# flasher.net
KiCad netlist of a schematic drawn in EAGLE
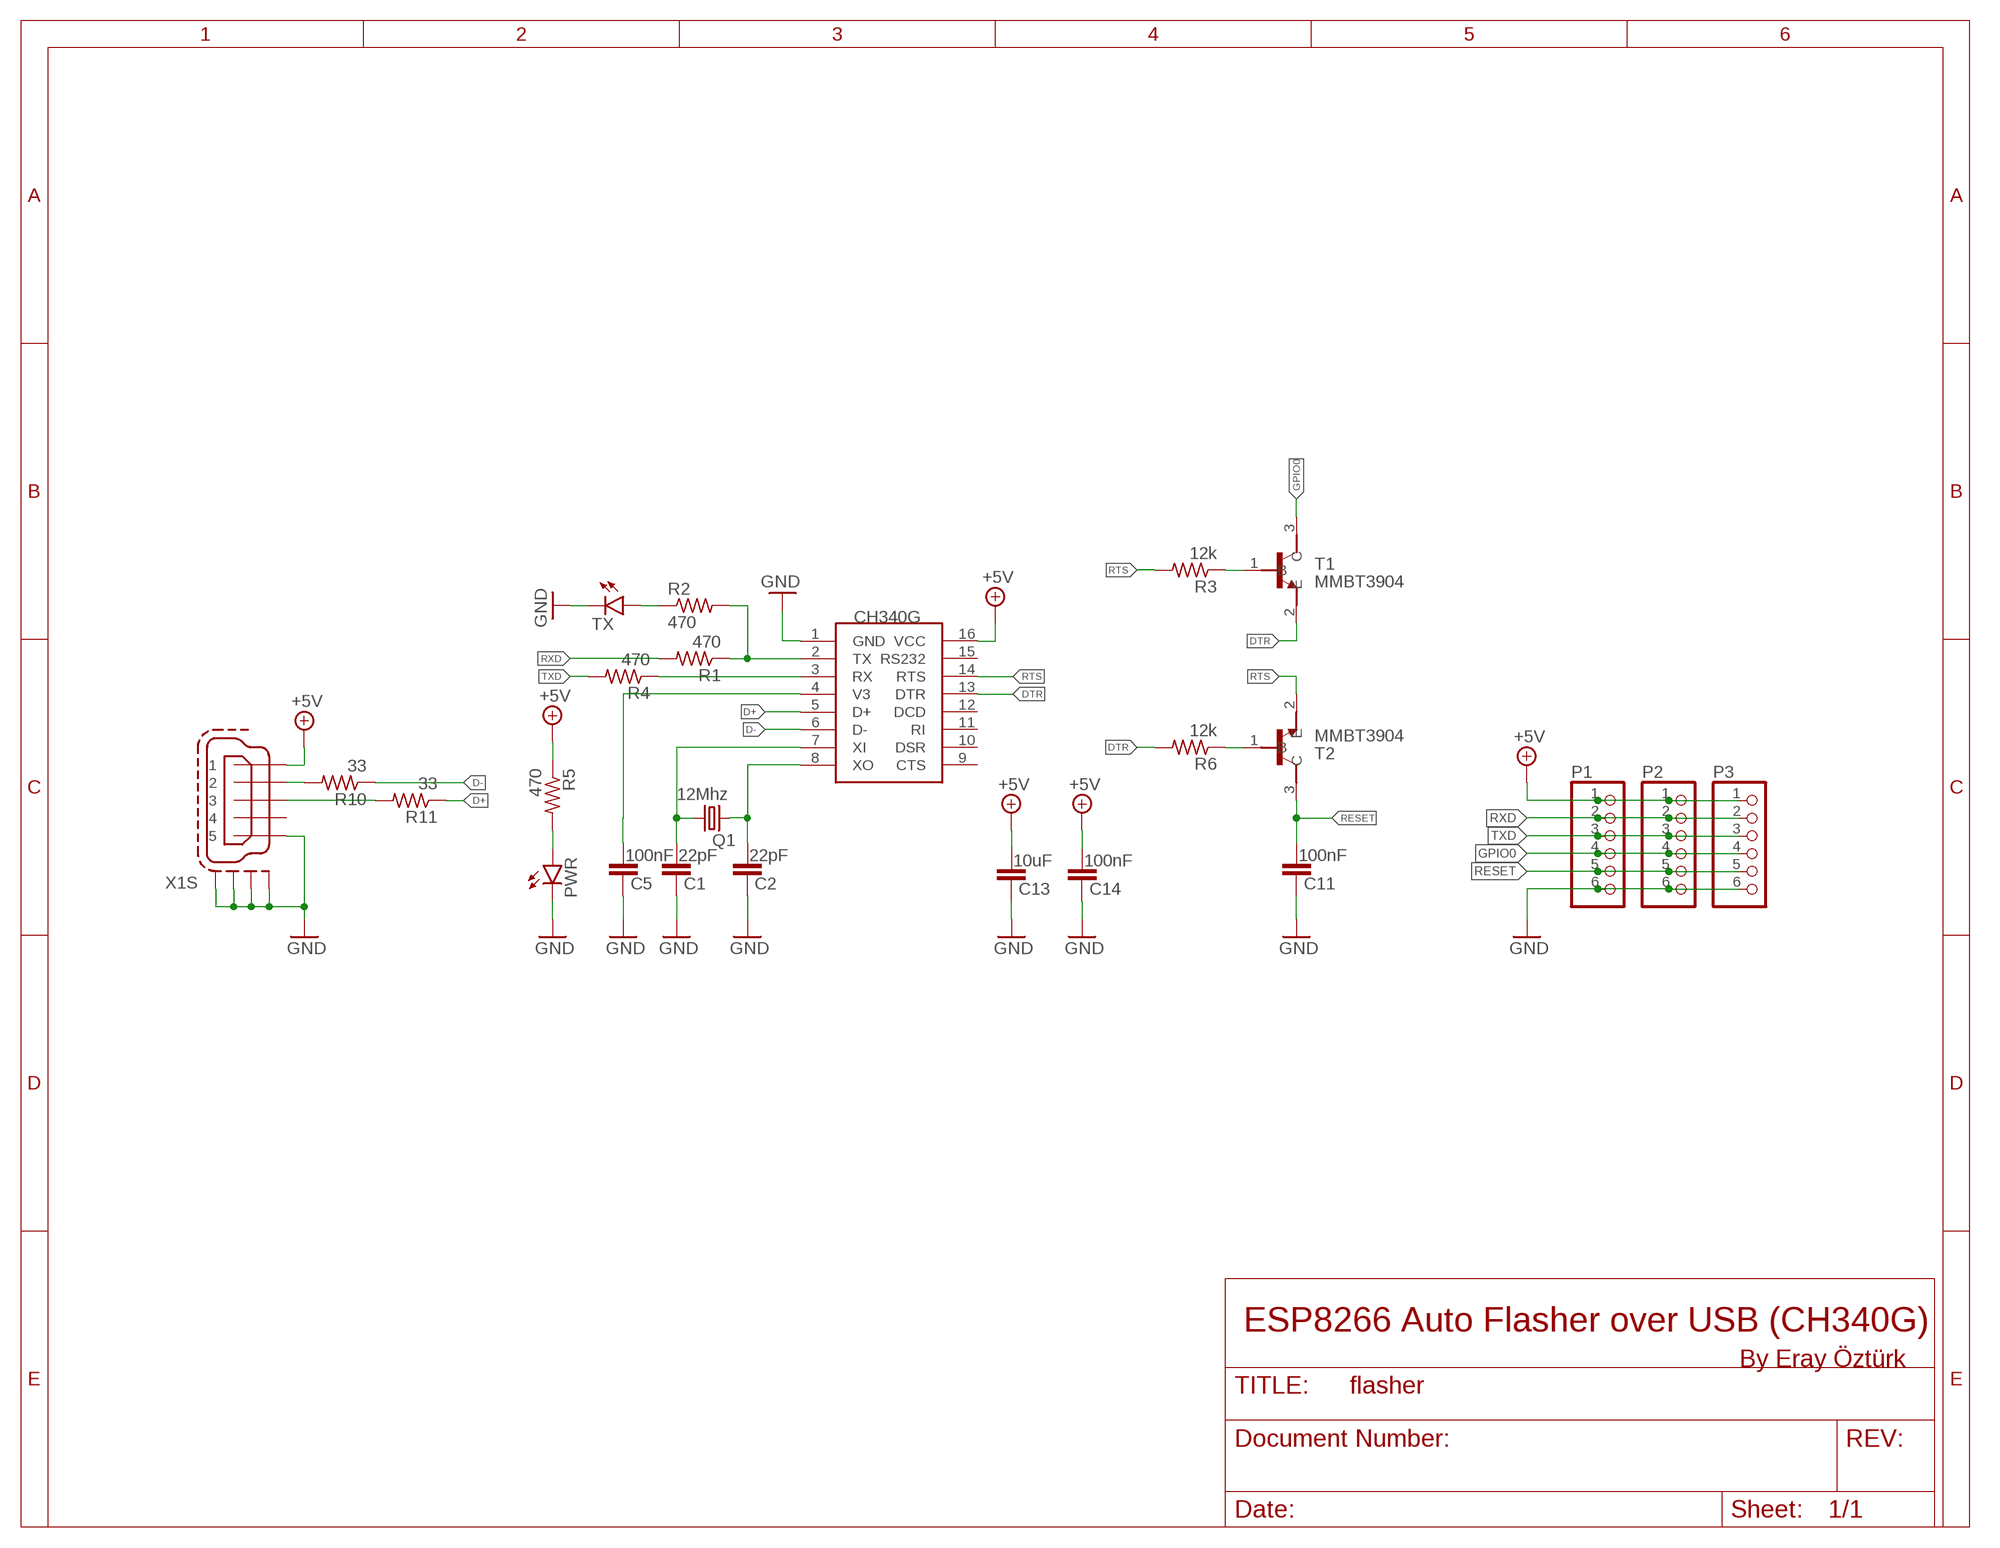
[diagram p0: schematic, sheet 1]

(export (version "E")
  (design (tool "Eeschema 10.0.6"))
  (components
    (comp (ref "C1")
      (value "22pF")
      (footprint "eagle-import:C0805")
      (libsource (lib "eagle-import") (part "C-EUC0805"))
    )
    (comp (ref "C2")
      (value "22pF")
      (footprint "eagle-import:C0805")
      (libsource (lib "eagle-import") (part "C-EUC0805"))
    )
    (comp (ref "C5")
      (value "100nF")
      (footprint "eagle-import:C0805")
      (libsource (lib "eagle-import") (part "C-EUC0805"))
    )
    (comp (ref "C11")
      (value "100nF")
      (footprint "eagle-import:C0805")
      (libsource (lib "eagle-import") (part "C-EUC0805"))
    )
    (comp (ref "C13")
      (value "10uF")
      (footprint "eagle-import:C0805")
      (libsource (lib "eagle-import") (part "C-EUC0805"))
    )
    (comp (ref "C14")
      (value "100nF")
      (footprint "eagle-import:C0805")
      (libsource (lib "eagle-import") (part "C-EUC0805"))
    )
    (comp (ref "P1")
      (value "PINHD-1X6")
      (footprint "eagle-import:1X06")
      (libsource (lib "eagle-import") (part "PINHD-1X6"))
    )
    (comp (ref "P2")
      (value "PINHD-1X6")
      (footprint "eagle-import:1X06")
      (libsource (lib "eagle-import") (part "PINHD-1X6"))
    )
    (comp (ref "P3")
      (value "PINHD-1X6")
      (footprint "eagle-import:1X06")
      (libsource (lib "eagle-import") (part "PINHD-1X6"))
    )
    (comp (ref "PWR")
      (value "LEDCHIP-LED0805")
      (footprint "eagle-import:CHIP-LED0805")
      (libsource (lib "eagle-import") (part "LEDCHIP-LED0805"))
    )
    (comp (ref "Q1")
      (value "12Mhz")
      (footprint "eagle-import:HC49_S")
      (libsource (lib "eagle-import") (part "CRYSTALHC49S"))
    )
    (comp (ref "R1")
      (value "470")
      (footprint "eagle-import:M0805")
      (libsource (lib "eagle-import") (part "R-US_M0805"))
    )
    (comp (ref "R2")
      (value "470")
      (footprint "eagle-import:M0805")
      (libsource (lib "eagle-import") (part "R-US_M0805"))
    )
    (comp (ref "R3")
      (value "12k")
      (footprint "eagle-import:M0805")
      (libsource (lib "eagle-import") (part "R-US_M0805"))
    )
    (comp (ref "R4")
      (value "470")
      (footprint "eagle-import:M0805")
      (libsource (lib "eagle-import") (part "R-US_M0805"))
    )
    (comp (ref "R5")
      (value "470")
      (footprint "eagle-import:M0805")
      (libsource (lib "eagle-import") (part "R-US_M0805"))
    )
    (comp (ref "R6")
      (value "12k")
      (footprint "eagle-import:M0805")
      (libsource (lib "eagle-import") (part "R-US_M0805"))
    )
    (comp (ref "R10")
      (value "33")
      (footprint "eagle-import:M0805")
      (libsource (lib "eagle-import") (part "R-US_M0805"))
    )
    (comp (ref "R11")
      (value "33")
      (footprint "eagle-import:M0805")
      (libsource (lib "eagle-import") (part "R-US_M0805"))
    )
    (comp (ref "T1")
      (value "MMBT3904")
      (footprint "eagle-import:SOT95P240X120-3N")
      (fields (field (name "MF") "STMicroelectronics"))
      (libsource (lib "eagle-import") (part "MMBT3904"))
    )
    (comp (ref "T2")
      (value "MMBT3904")
      (footprint "eagle-import:SOT95P240X120-3N")
      (fields (field (name "MF") "STMicroelectronics"))
      (libsource (lib "eagle-import") (part "MMBT3904"))
    )
    (comp (ref "TX")
      (value "LEDCHIP-LED0805")
      (footprint "eagle-import:CHIP-LED0805")
      (libsource (lib "eagle-import") (part "LEDCHIP-LED0805"))
    )
    (comp (ref "U1")
      (value "CH340G")
      (footprint "eagle-import:SOIC16")
      (libsource (lib "eagle-import") (part "CH340G"))
    )
    (comp (ref "X1")
      (value "MINI-USB-SCHIELD-32005-201")
      (footprint "eagle-import:32005-201")
      (libsource (lib "eagle-import") (part "MINI-USB-SCHIELD-32005-201"))
    )
  )
  (nets
    (net (code "1") (name "+5V") (class "Default")
      (node (ref "C13") (pin "2") (pinfunction "2_2") (pintype "passive"))
      (node (ref "C14") (pin "2") (pinfunction "2_2") (pintype "passive"))
      (node (ref "P1") (pin "1") (pinfunction "1_1") (pintype "passive"))
      (node (ref "P2") (pin "1") (pinfunction "1_1") (pintype "passive"))
      (node (ref "P3") (pin "1") (pinfunction "1_1") (pintype "passive"))
      (node (ref "R5") (pin "1") (pinfunction "1_1") (pintype "passive"))
      (node (ref "U1") (pin "16") (pinfunction "VCC_16") (pintype "bidirectional"))
      (node (ref "X1") (pin "1") (pinfunction "1_1") (pintype "passive"))
    )
    (net (code "2") (name "D+") (class "Default")
      (node (ref "R11") (pin "1") (pinfunction "1_1") (pintype "passive"))
      (node (ref "U1") (pin "5") (pinfunction "D+_5") (pintype "bidirectional"))
    )
    (net (code "3") (name "D-") (class "Default")
      (node (ref "R10") (pin "1") (pinfunction "1_1") (pintype "passive"))
      (node (ref "U1") (pin "6") (pinfunction "D-_6") (pintype "bidirectional"))
    )
    (net (code "4") (name "DTR") (class "Default")
      (node (ref "R6") (pin "2") (pinfunction "2_2") (pintype "passive"))
      (node (ref "T1") (pin "2") (pinfunction "E_2") (pintype "passive"))
      (node (ref "U1") (pin "13") (pinfunction "DTR_13") (pintype "bidirectional"))
    )
    (net (code "5") (name "GND") (class "Default")
      (node (ref "C1") (pin "1") (pinfunction "1_1") (pintype "passive"))
      (node (ref "C11") (pin "1") (pinfunction "1_1") (pintype "passive"))
      (node (ref "C13") (pin "1") (pinfunction "1_1") (pintype "passive"))
      (node (ref "C14") (pin "1") (pinfunction "1_1") (pintype "passive"))
      (node (ref "C2") (pin "1") (pinfunction "1_1") (pintype "passive"))
      (node (ref "C5") (pin "1") (pinfunction "1_1") (pintype "passive"))
      (node (ref "P1") (pin "6") (pinfunction "6_6") (pintype "passive"))
      (node (ref "P2") (pin "6") (pinfunction "6_6") (pintype "passive"))
      (node (ref "P3") (pin "6") (pinfunction "6_6") (pintype "passive"))
      (node (ref "PWR") (pin "C") (pinfunction "C_C") (pintype "passive"))
      (node (ref "TX") (pin "C") (pinfunction "C_C") (pintype "passive"))
      (node (ref "U1") (pin "1") (pinfunction "GND_1") (pintype "bidirectional"))
      (node (ref "X1") (pin "5") (pinfunction "5_5") (pintype "passive"))
      (node (ref "X1") (pin "M1") (pinfunction "S1_M1") (pintype "passive"))
      (node (ref "X1") (pin "M2") (pinfunction "S2_M2") (pintype "passive"))
      (node (ref "X1") (pin "M3") (pinfunction "S3_M3") (pintype "passive"))
      (node (ref "X1") (pin "M4") (pinfunction "S4_M4") (pintype "passive"))
    )
    (net (code "6") (name "GPIO0") (class "Default")
      (node (ref "P1") (pin "4") (pinfunction "4_4") (pintype "passive"))
      (node (ref "P2") (pin "4") (pinfunction "4_4") (pintype "passive"))
      (node (ref "P3") (pin "4") (pinfunction "4_4") (pintype "passive"))
      (node (ref "T1") (pin "3") (pinfunction "C_3") (pintype "passive"))
    )
    (net (code "7") (name "Net-(PWR-PadA)") (class "Default")
      (node (ref "PWR") (pin "A") (pinfunction "A_A") (pintype "passive"))
      (node (ref "R5") (pin "2") (pinfunction "2_2") (pintype "passive"))
    )
    (net (code "8") (name "Net-(R2-Pad1)") (class "Default")
      (node (ref "R2") (pin "1") (pinfunction "1_1") (pintype "passive"))
      (node (ref "TX") (pin "A") (pinfunction "A_A") (pintype "passive"))
    )
    (net (code "9") (name "Net-(R10-Pad2)") (class "Default")
      (node (ref "R10") (pin "2") (pinfunction "2_2") (pintype "passive"))
      (node (ref "X1") (pin "2") (pinfunction "2_2") (pintype "passive"))
    )
    (net (code "10") (name "Net-(R11-Pad2)") (class "Default")
      (node (ref "R11") (pin "2") (pinfunction "2_2") (pintype "passive"))
      (node (ref "X1") (pin "3") (pinfunction "3_3") (pintype "passive"))
    )
    (net (code "11") (name "Net-(T1-B)") (class "Default")
      (node (ref "R3") (pin "1") (pinfunction "1_1") (pintype "passive"))
      (node (ref "T1") (pin "1") (pinfunction "B_1") (pintype "passive"))
    )
    (net (code "12") (name "Net-(T2-B)") (class "Default")
      (node (ref "R6") (pin "1") (pinfunction "1_1") (pintype "passive"))
      (node (ref "T2") (pin "1") (pinfunction "B_1") (pintype "passive"))
    )
    (net (code "13") (name "Net-(U1-RX)") (class "Default")
      (node (ref "R4") (pin "1") (pinfunction "1_1") (pintype "passive"))
      (node (ref "U1") (pin "3") (pinfunction "RX_3") (pintype "bidirectional"))
    )
    (net (code "14") (name "Net-(U1-TX)") (class "Default")
      (node (ref "R1") (pin "1") (pinfunction "1_1") (pintype "passive"))
      (node (ref "R2") (pin "2") (pinfunction "2_2") (pintype "passive"))
      (node (ref "U1") (pin "2") (pinfunction "TX_2") (pintype "bidirectional"))
    )
    (net (code "15") (name "Net-(U1-V3)") (class "Default")
      (node (ref "C5") (pin "2") (pinfunction "2_2") (pintype "passive"))
      (node (ref "U1") (pin "4") (pinfunction "V3_4") (pintype "bidirectional"))
    )
    (net (code "16") (name "Net-(U1-XI)") (class "Default")
      (node (ref "C1") (pin "2") (pinfunction "2_2") (pintype "passive"))
      (node (ref "Q1") (pin "1") (pinfunction "1_1") (pintype "passive"))
      (node (ref "U1") (pin "7") (pinfunction "XI_7") (pintype "bidirectional"))
    )
    (net (code "17") (name "Net-(U1-XO)") (class "Default")
      (node (ref "C2") (pin "2") (pinfunction "2_2") (pintype "passive"))
      (node (ref "Q1") (pin "2") (pinfunction "2_2") (pintype "passive"))
      (node (ref "U1") (pin "8") (pinfunction "XO_8") (pintype "bidirectional"))
    )
    (net (code "18") (name "RESET") (class "Default")
      (node (ref "C11") (pin "2") (pinfunction "2_2") (pintype "passive"))
      (node (ref "P1") (pin "5") (pinfunction "5_5") (pintype "passive"))
      (node (ref "P2") (pin "5") (pinfunction "5_5") (pintype "passive"))
      (node (ref "P3") (pin "5") (pinfunction "5_5") (pintype "passive"))
      (node (ref "T2") (pin "3") (pinfunction "C_3") (pintype "passive"))
    )
    (net (code "19") (name "RTS") (class "Default")
      (node (ref "R3") (pin "2") (pinfunction "2_2") (pintype "passive"))
      (node (ref "T2") (pin "2") (pinfunction "E_2") (pintype "passive"))
      (node (ref "U1") (pin "14") (pinfunction "RTS_14") (pintype "bidirectional"))
    )
    (net (code "20") (name "RXD") (class "Default")
      (node (ref "P1") (pin "2") (pinfunction "2_2") (pintype "passive"))
      (node (ref "P2") (pin "2") (pinfunction "2_2") (pintype "passive"))
      (node (ref "P3") (pin "2") (pinfunction "2_2") (pintype "passive"))
      (node (ref "R1") (pin "2") (pinfunction "2_2") (pintype "passive"))
    )
    (net (code "21") (name "TXD") (class "Default")
      (node (ref "P1") (pin "3") (pinfunction "3_3") (pintype "passive"))
      (node (ref "P2") (pin "3") (pinfunction "3_3") (pintype "passive"))
      (node (ref "P3") (pin "3") (pinfunction "3_3") (pintype "passive"))
      (node (ref "R4") (pin "2") (pinfunction "2_2") (pintype "passive"))
    )
    (net (code "22") (name "unconnected-(U1-CTS-Pad9)") (class "Default")
      (node (ref "U1") (pin "9") (pinfunction "CTS_9") (pintype "bidirectional"))
    )
    (net (code "23") (name "unconnected-(U1-DCD-Pad12)") (class "Default")
      (node (ref "U1") (pin "12") (pinfunction "DCD_12") (pintype "bidirectional"))
    )
    (net (code "24") (name "unconnected-(U1-DSR-Pad10)") (class "Default")
      (node (ref "U1") (pin "10") (pinfunction "DSR_10") (pintype "bidirectional"))
    )
    (net (code "25") (name "unconnected-(U1-RI-Pad11)") (class "Default")
      (node (ref "U1") (pin "11") (pinfunction "RI_11") (pintype "bidirectional"))
    )
    (net (code "26") (name "unconnected-(U1-RS232-Pad15)") (class "Default")
      (node (ref "U1") (pin "15") (pinfunction "RS232_15") (pintype "bidirectional"))
    )
    (net (code "27") (name "unconnected-(X1-Pad4)") (class "Default")
      (node (ref "X1") (pin "4") (pinfunction "4_4") (pintype "passive"))
    )
  )
)
